# sensors.net
KiCad netlist of a schematic drawn in Altium Designer
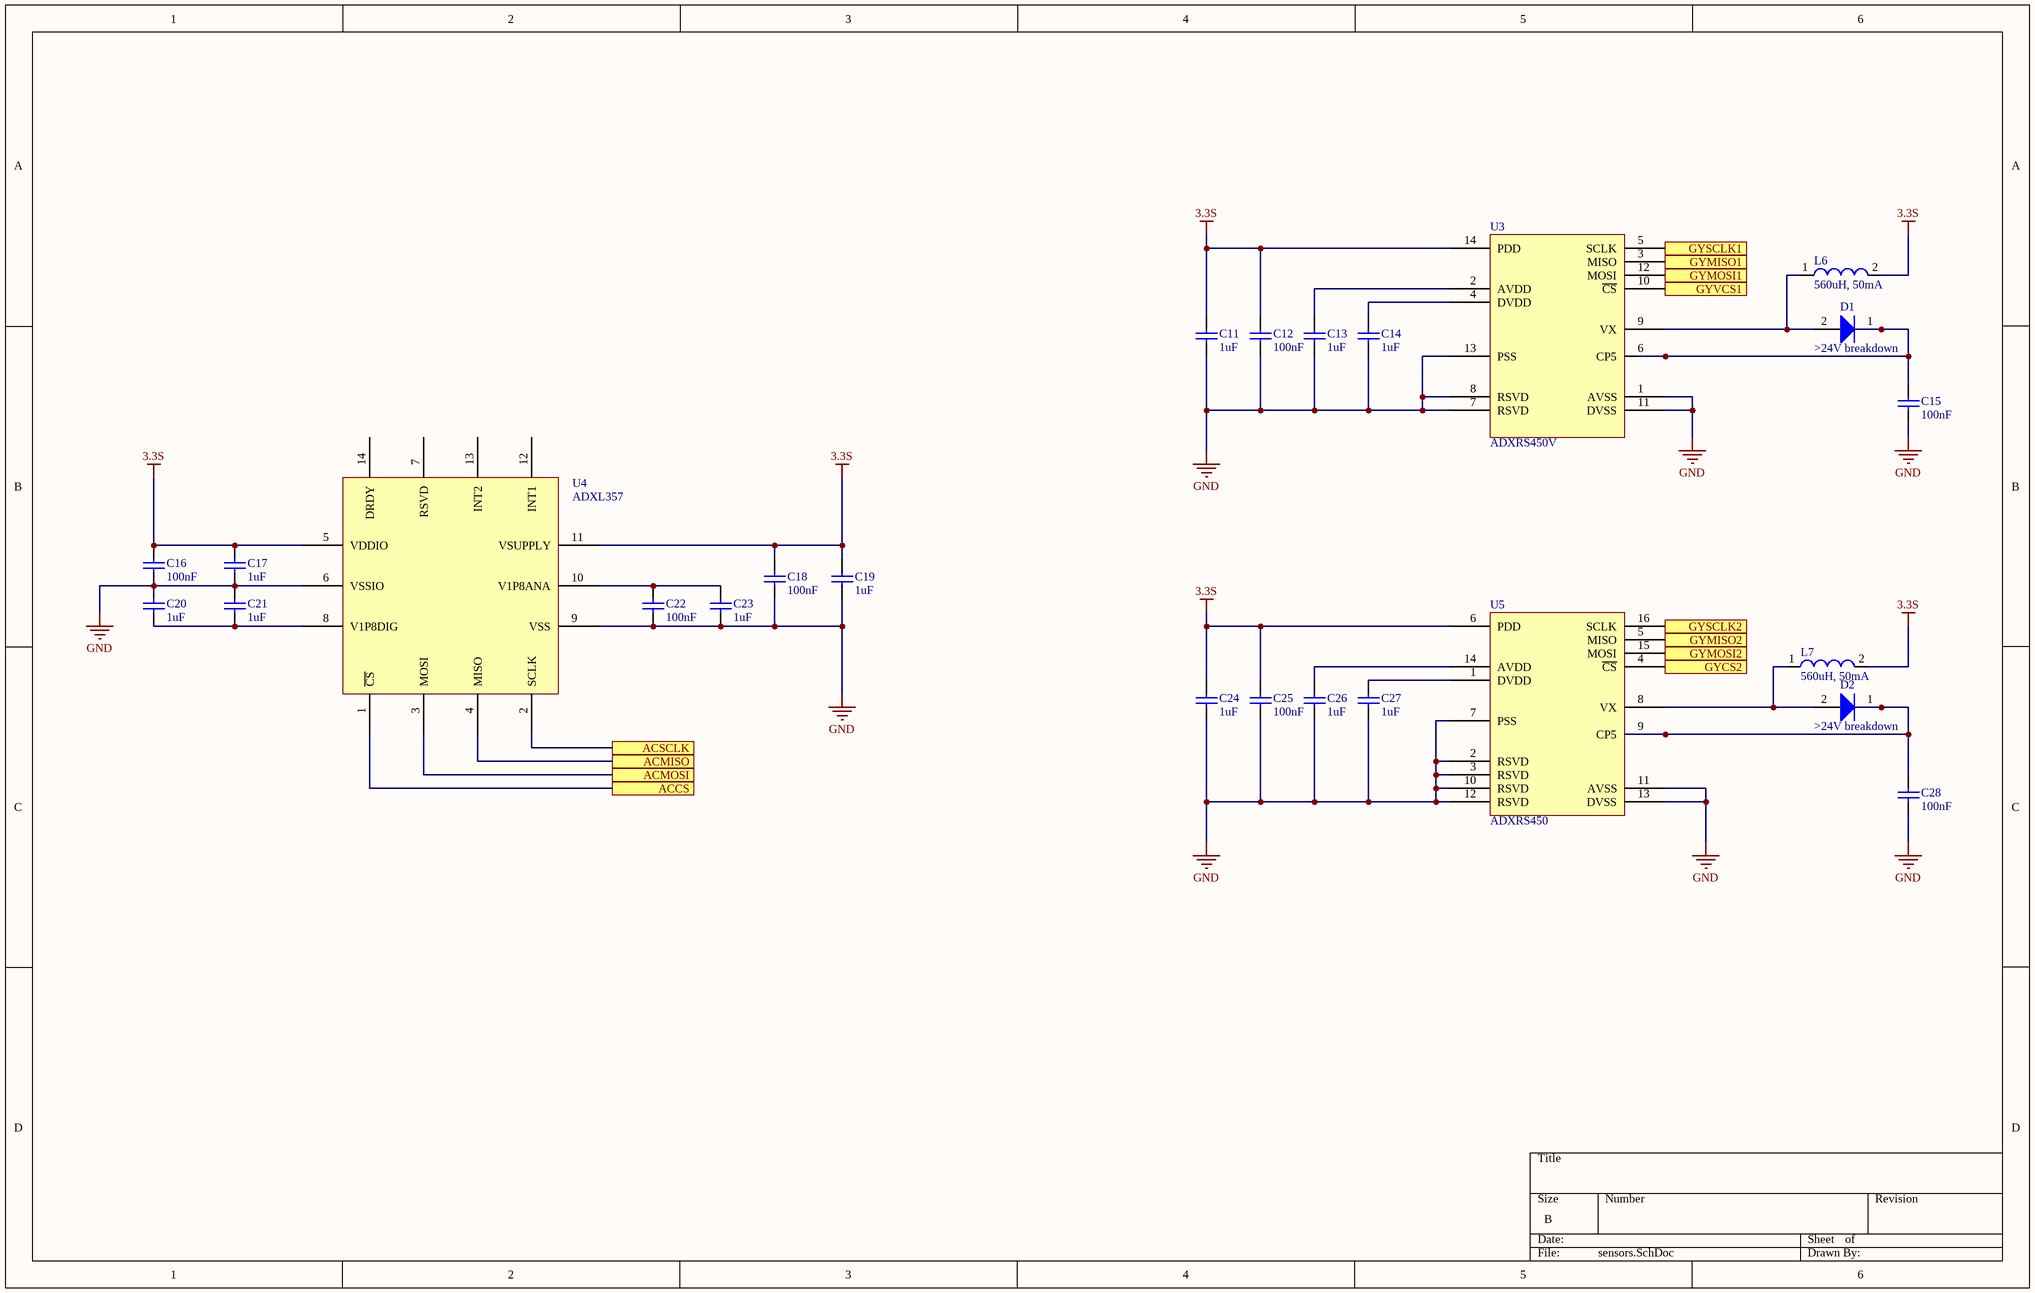
[diagram p0: sensors.SchDoc]

(export (version "E")
  (design (tool "Eeschema 10.0.6"))
  (components
    (comp (ref "C11")
      (value "1uF")
      (footprint "CAPC1709X95X35LL10T25")
      (description "Chip Capacitor, 1 uF, +/- 10%, 50 V, -55 to 125 degC, 0603 (1608 Metric), RoHS, Tape and Reel")
      (fields (field (name "MANUFACTURER") "Taiyo Yuden") (field (name "TOLERANCE") "10%"))
      (libsource (lib "Altium Content Vault") (part "CAP-NP-2"))
    )
    (comp (ref "C12")
      (value "100nF")
      (footprint "CAPC1608X90X40ML10T20")
      (fields (field (name "TOLERANCE") "±10%") (field (name "MANUFACTURER") "Yageo"))
      (libsource (lib "Altium Content Vault") (part "CAP-NP-2"))
    )
    (comp (ref "C13")
      (value "1uF")
      (footprint "CAPC1709X95X35LL10T25")
      (description "Chip Capacitor, 1 uF, +/- 10%, 50 V, -55 to 125 degC, 0603 (1608 Metric), RoHS, Tape and Reel")
      (fields (field (name "MANUFACTURER") "Taiyo Yuden") (field (name "TOLERANCE") "10%"))
      (libsource (lib "Altium Content Vault") (part "CAP-NP-2"))
    )
    (comp (ref "C14")
      (value "1uF")
      (footprint "CAPC1709X95X35LL10T25")
      (description "Chip Capacitor, 1 uF, +/- 10%, 50 V, -55 to 125 degC, 0603 (1608 Metric), RoHS, Tape and Reel")
      (fields (field (name "MANUFACTURER") "Taiyo Yuden") (field (name "TOLERANCE") "10%"))
      (libsource (lib "Altium Content Vault") (part "CAP-NP-2"))
    )
    (comp (ref "C15")
      (value "100nF")
      (footprint "CAPC1608X90X40ML10T20")
      (fields (field (name "TOLERANCE") "±10%") (field (name "MANUFACTURER") "Yageo"))
      (libsource (lib "Altium Content Vault") (part "CAP-NP-2"))
    )
    (comp (ref "C16")
      (value "100nF")
      (footprint "CAPC1608X90X40ML10T20")
      (fields (field (name "TOLERANCE") "±10%") (field (name "MANUFACTURER") "Yageo"))
      (libsource (lib "Altium Content Vault") (part "CAP-NP-2"))
    )
    (comp (ref "C17")
      (value "1uF")
      (footprint "CAPC1709X95X35LL10T25")
      (description "Chip Capacitor, 1 uF, +/- 10%, 50 V, -55 to 125 degC, 0603 (1608 Metric), RoHS, Tape and Reel")
      (fields (field (name "MANUFACTURER") "Taiyo Yuden") (field (name "TOLERANCE") "10%"))
      (libsource (lib "Altium Content Vault") (part "CAP-NP-2"))
    )
    (comp (ref "C18")
      (value "100nF")
      (footprint "CAPC1608X90X40ML10T20")
      (fields (field (name "TOLERANCE") "±10%") (field (name "MANUFACTURER") "Yageo"))
      (libsource (lib "Altium Content Vault") (part "CAP-NP-2"))
    )
    (comp (ref "C19")
      (value "1uF")
      (footprint "CAPC1709X95X35LL10T25")
      (description "Chip Capacitor, 1 uF, +/- 10%, 50 V, -55 to 125 degC, 0603 (1608 Metric), RoHS, Tape and Reel")
      (fields (field (name "MANUFACTURER") "Taiyo Yuden") (field (name "TOLERANCE") "10%"))
      (libsource (lib "Altium Content Vault") (part "CAP-NP-2"))
    )
    (comp (ref "C20")
      (value "1uF")
      (footprint "CAPC1709X95X35LL10T25")
      (description "Chip Capacitor, 1 uF, +/- 10%, 50 V, -55 to 125 degC, 0603 (1608 Metric), RoHS, Tape and Reel")
      (fields (field (name "MANUFACTURER") "Taiyo Yuden") (field (name "TOLERANCE") "10%"))
      (libsource (lib "Altium Content Vault") (part "CAP-NP-2"))
    )
    (comp (ref "C21")
      (value "1uF")
      (footprint "CAPC1709X95X35LL10T25")
      (description "Chip Capacitor, 1 uF, +/- 10%, 50 V, -55 to 125 degC, 0603 (1608 Metric), RoHS, Tape and Reel")
      (fields (field (name "MANUFACTURER") "Taiyo Yuden") (field (name "TOLERANCE") "10%"))
      (libsource (lib "Altium Content Vault") (part "CAP-NP-2"))
    )
    (comp (ref "C22")
      (value "100nF")
      (footprint "CAPC1608X90X40ML10T20")
      (fields (field (name "TOLERANCE") "±10%") (field (name "MANUFACTURER") "Yageo"))
      (libsource (lib "Altium Content Vault") (part "CAP-NP-2"))
    )
    (comp (ref "C23")
      (value "1uF")
      (footprint "CAPC1709X95X35LL10T25")
      (description "Chip Capacitor, 1 uF, +/- 10%, 50 V, -55 to 125 degC, 0603 (1608 Metric), RoHS, Tape and Reel")
      (fields (field (name "MANUFACTURER") "Taiyo Yuden") (field (name "TOLERANCE") "10%"))
      (libsource (lib "Altium Content Vault") (part "CAP-NP-2"))
    )
    (comp (ref "C24")
      (value "1uF")
      (footprint "CAPC1709X95X35LL10T25")
      (description "Chip Capacitor, 1 uF, +/- 10%, 50 V, -55 to 125 degC, 0603 (1608 Metric), RoHS, Tape and Reel")
      (fields (field (name "MANUFACTURER") "Taiyo Yuden") (field (name "TOLERANCE") "10%"))
      (libsource (lib "Altium Content Vault") (part "CAP-NP-2"))
    )
    (comp (ref "C25")
      (value "100nF")
      (footprint "CAPC1608X90X40ML10T20")
      (fields (field (name "TOLERANCE") "±10%") (field (name "MANUFACTURER") "Yageo"))
      (libsource (lib "Altium Content Vault") (part "CAP-NP-2"))
    )
    (comp (ref "C26")
      (value "1uF")
      (footprint "CAPC1709X95X35LL10T25")
      (description "Chip Capacitor, 1 uF, +/- 10%, 50 V, -55 to 125 degC, 0603 (1608 Metric), RoHS, Tape and Reel")
      (fields (field (name "MANUFACTURER") "Taiyo Yuden") (field (name "TOLERANCE") "10%"))
      (libsource (lib "Altium Content Vault") (part "CAP-NP-2"))
    )
    (comp (ref "C27")
      (value "1uF")
      (footprint "CAPC1709X95X35LL10T25")
      (description "Chip Capacitor, 1 uF, +/- 10%, 50 V, -55 to 125 degC, 0603 (1608 Metric), RoHS, Tape and Reel")
      (fields (field (name "MANUFACTURER") "Taiyo Yuden") (field (name "TOLERANCE") "10%"))
      (libsource (lib "Altium Content Vault") (part "CAP-NP-2"))
    )
    (comp (ref "C28")
      (value "100nF")
      (footprint "CAPC1608X90X40ML10T20")
      (fields (field (name "TOLERANCE") "±10%") (field (name "MANUFACTURER") "Yageo"))
      (libsource (lib "Altium Content Vault") (part "CAP-NP-2"))
    )
    (comp (ref "D1")
      (value ">24V breakdown")
      (footprint "ONSC-SOD-323-2-477-02_V")
      (description "Schottky Barrier Diode, 2-Pin SOD-323, Pb-Free, Tape and Reel")
      (fields (field (name "PARTNUMBER") "BAT54HT1G") (field (name "MANUFACTURER") "On Semiconductor"))
      (libsource (lib "Altium Content Vault") (part "ONSC-D-K1A2-2"))
    )
    (comp (ref "D2")
      (value ">24V breakdown")
      (footprint "ONSC-SOD-323-2-477-02_V")
      (description "Schottky Barrier Diode, 2-Pin SOD-323, Pb-Free, Tape and Reel")
      (fields (field (name "PARTNUMBER") "BAT54HT1G") (field (name "MANUFACTURER") "On Semiconductor"))
      (libsource (lib "Altium Content Vault") (part "ONSC-D-K1A2-2"))
    )
    (comp (ref "L6")
      (value "560uH, 50mA")
      (footprint "WE-PD-L")
      (description "SMD-Shielded Power Inductor WE-PD, L = 560 µH")
      (libsource (lib "Altium Content Vault") (part "PAS-IND-INDUCTOR-2"))
    )
    (comp (ref "L7")
      (value "560uH, 50mA")
      (footprint "WE-PD-L")
      (description "SMD-Shielded Power Inductor WE-PD, L = 560 µH")
      (libsource (lib "Altium Content Vault") (part "PAS-IND-INDUCTOR-2"))
    )
    (comp (ref "U3")
      (value "ADXRS450V")
      (footprint "LCC127P900X400X915-14N")
      (libsource (lib "ADXRS450") (part "ADXRS450V"))
    )
    (comp (ref "U4")
      (value "ADXL357")
      (footprint "LCCS127P605X560X220-14N")
      (libsource (lib "ADXL357") (part "ADXL357"))
    )
    (comp (ref "U5")
      (value "ADXRS450")
      (footprint "SOIC127P1040X373-16N")
      (libsource (lib "ADXRS450") (part "ADXRS450"))
    )
  )
  (nets
    (net (code "1") (name "/ACCS") (class "Default")
      (node (ref "U4") (pin "1") (pinfunction "~{CS}_1") (pintype "passive"))
    )
    (net (code "2") (name "/ACMISO") (class "Default")
      (node (ref "U4") (pin "4") (pinfunction "MISO_4") (pintype "passive"))
    )
    (net (code "3") (name "/ACMOSI") (class "Default")
      (node (ref "U4") (pin "3") (pinfunction "MOSI_3") (pintype "passive"))
    )
    (net (code "4") (name "/ACSCLK") (class "Default")
      (node (ref "U4") (pin "2") (pinfunction "SCLK_2") (pintype "passive"))
    )
    (net (code "5") (name "/GYCS2") (class "Default")
      (node (ref "U5") (pin "4") (pinfunction "~{CS}_4") (pintype "passive"))
    )
    (net (code "6") (name "/GYMISO1") (class "Default")
      (node (ref "U3") (pin "3") (pinfunction "MISO_3") (pintype "passive"))
    )
    (net (code "7") (name "/GYMISO2") (class "Default")
      (node (ref "U5") (pin "5") (pinfunction "MISO_5") (pintype "passive"))
    )
    (net (code "8") (name "/GYMOSI1") (class "Default")
      (node (ref "U3") (pin "12") (pinfunction "MOSI_12") (pintype "passive"))
    )
    (net (code "9") (name "/GYMOSI2") (class "Default")
      (node (ref "U5") (pin "15") (pinfunction "MOSI_15") (pintype "passive"))
    )
    (net (code "10") (name "/GYSCLK1") (class "Default")
      (node (ref "U3") (pin "5") (pinfunction "SCLK_5") (pintype "passive"))
    )
    (net (code "11") (name "/GYSCLK2") (class "Default")
      (node (ref "U5") (pin "16") (pinfunction "SCLK_16") (pintype "passive"))
    )
    (net (code "12") (name "/GYVCS1") (class "Default")
      (node (ref "U3") (pin "10") (pinfunction "~{CS}_10") (pintype "passive"))
    )
    (net (code "13") (name "3.3S") (class "Default")
      (node (ref "C11") (pin "2") (pinfunction "2_2") (pintype "passive"))
      (node (ref "C12") (pin "2") (pinfunction "2_2") (pintype "passive"))
      (node (ref "C16") (pin "1") (pinfunction "1_1") (pintype "passive"))
      (node (ref "C17") (pin "2") (pinfunction "2_2") (pintype "passive"))
      (node (ref "C18") (pin "1") (pinfunction "1_1") (pintype "passive"))
      (node (ref "C19") (pin "2") (pinfunction "2_2") (pintype "passive"))
      (node (ref "C24") (pin "2") (pinfunction "2_2") (pintype "passive"))
      (node (ref "C25") (pin "2") (pinfunction "2_2") (pintype "passive"))
      (node (ref "L6") (pin "2") (pinfunction "2_2") (pintype "passive"))
      (node (ref "L7") (pin "2") (pinfunction "2_2") (pintype "passive"))
      (node (ref "U3") (pin "14") (pinfunction "PDD_14") (pintype "passive"))
      (node (ref "U4") (pin "11") (pinfunction "VSUPPLY_11") (pintype "passive"))
      (node (ref "U4") (pin "5") (pinfunction "VDDIO_5") (pintype "passive"))
      (node (ref "U5") (pin "6") (pinfunction "PDD_6") (pintype "passive"))
    )
    (net (code "14") (name "GND") (class "Default")
      (node (ref "C11") (pin "1") (pinfunction "1_1") (pintype "passive"))
      (node (ref "C12") (pin "1") (pinfunction "1_1") (pintype "passive"))
      (node (ref "C13") (pin "1") (pinfunction "1_1") (pintype "passive"))
      (node (ref "C14") (pin "1") (pinfunction "1_1") (pintype "passive"))
      (node (ref "C15") (pin "1") (pinfunction "1_1") (pintype "passive"))
      (node (ref "C16") (pin "2") (pinfunction "2_2") (pintype "passive"))
      (node (ref "C17") (pin "1") (pinfunction "1_1") (pintype "passive"))
      (node (ref "C18") (pin "2") (pinfunction "2_2") (pintype "passive"))
      (node (ref "C19") (pin "1") (pinfunction "1_1") (pintype "passive"))
      (node (ref "C20") (pin "2") (pinfunction "2_2") (pintype "passive"))
      (node (ref "C21") (pin "2") (pinfunction "2_2") (pintype "passive"))
      (node (ref "C22") (pin "2") (pinfunction "2_2") (pintype "passive"))
      (node (ref "C23") (pin "1") (pinfunction "1_1") (pintype "passive"))
      (node (ref "C24") (pin "1") (pinfunction "1_1") (pintype "passive"))
      (node (ref "C25") (pin "1") (pinfunction "1_1") (pintype "passive"))
      (node (ref "C26") (pin "1") (pinfunction "1_1") (pintype "passive"))
      (node (ref "C27") (pin "1") (pinfunction "1_1") (pintype "passive"))
      (node (ref "C28") (pin "1") (pinfunction "1_1") (pintype "passive"))
      (node (ref "U3") (pin "1") (pinfunction "AVSS_1") (pintype "passive"))
      (node (ref "U3") (pin "11") (pinfunction "DVSS_11") (pintype "passive"))
      (node (ref "U3") (pin "13") (pinfunction "PSS_13") (pintype "passive"))
      (node (ref "U3") (pin "7") (pinfunction "RSVD_7") (pintype "passive"))
      (node (ref "U3") (pin "8") (pinfunction "RSVD_8") (pintype "passive"))
      (node (ref "U4") (pin "6") (pinfunction "VSSIO_6") (pintype "passive"))
      (node (ref "U4") (pin "9") (pinfunction "VSS_9") (pintype "passive"))
      (node (ref "U5") (pin "10") (pinfunction "RSVD_10") (pintype "passive"))
      (node (ref "U5") (pin "11") (pinfunction "AVSS_11") (pintype "passive"))
      (node (ref "U5") (pin "12") (pinfunction "RSVD_12") (pintype "passive"))
      (node (ref "U5") (pin "13") (pinfunction "DVSS_13") (pintype "passive"))
      (node (ref "U5") (pin "2") (pinfunction "RSVD_2") (pintype "passive"))
      (node (ref "U5") (pin "3") (pinfunction "RSVD_3") (pintype "passive"))
      (node (ref "U5") (pin "7") (pinfunction "PSS_7") (pintype "passive"))
    )
    (net (code "15") (name "Net-(D1-A)") (class "Default")
      (node (ref "D1") (pin "2") (pinfunction "A_2") (pintype "passive"))
      (node (ref "L6") (pin "1") (pinfunction "1_1") (pintype "passive"))
      (node (ref "U3") (pin "9") (pinfunction "VX_9") (pintype "passive"))
    )
    (net (code "16") (name "Net-(D1-K)") (class "Default")
      (node (ref "C15") (pin "2") (pinfunction "2_2") (pintype "passive"))
      (node (ref "D1") (pin "1") (pinfunction "K_1") (pintype "passive"))
      (node (ref "U3") (pin "6") (pinfunction "CP5_6") (pintype "passive"))
    )
    (net (code "17") (name "Net-(D2-A)") (class "Default")
      (node (ref "D2") (pin "2") (pinfunction "A_2") (pintype "passive"))
      (node (ref "L7") (pin "1") (pinfunction "1_1") (pintype "passive"))
      (node (ref "U5") (pin "8") (pinfunction "VX_8") (pintype "passive"))
    )
    (net (code "18") (name "Net-(D2-K)") (class "Default")
      (node (ref "C28") (pin "2") (pinfunction "2_2") (pintype "passive"))
      (node (ref "D2") (pin "1") (pinfunction "K_1") (pintype "passive"))
      (node (ref "U5") (pin "9") (pinfunction "CP5_9") (pintype "passive"))
    )
    (net (code "19") (name "Net-(U3-AVDD)") (class "Default")
      (node (ref "C13") (pin "2") (pinfunction "2_2") (pintype "passive"))
      (node (ref "U3") (pin "2") (pinfunction "AVDD_2") (pintype "passive"))
    )
    (net (code "20") (name "Net-(U3-DVDD)") (class "Default")
      (node (ref "C14") (pin "2") (pinfunction "2_2") (pintype "passive"))
      (node (ref "U3") (pin "4") (pinfunction "DVDD_4") (pintype "passive"))
    )
    (net (code "21") (name "Net-(U4-V1P8ANA)") (class "Default")
      (node (ref "C22") (pin "1") (pinfunction "1_1") (pintype "passive"))
      (node (ref "C23") (pin "2") (pinfunction "2_2") (pintype "passive"))
      (node (ref "U4") (pin "10") (pinfunction "V1P8ANA_10") (pintype "passive"))
    )
    (net (code "22") (name "Net-(U4-V1P8DIG)") (class "Default")
      (node (ref "C20") (pin "1") (pinfunction "1_1") (pintype "passive"))
      (node (ref "C21") (pin "1") (pinfunction "1_1") (pintype "passive"))
      (node (ref "U4") (pin "8") (pinfunction "V1P8DIG_8") (pintype "passive"))
    )
    (net (code "23") (name "Net-(U5-AVDD)") (class "Default")
      (node (ref "C26") (pin "2") (pinfunction "2_2") (pintype "passive"))
      (node (ref "U5") (pin "14") (pinfunction "AVDD_14") (pintype "passive"))
    )
    (net (code "24") (name "Net-(U5-DVDD)") (class "Default")
      (node (ref "C27") (pin "2") (pinfunction "2_2") (pintype "passive"))
      (node (ref "U5") (pin "1") (pinfunction "DVDD_1") (pintype "passive"))
    )
    (net (code "25") (name "unconnected-(U4-DRDY-Pad14)") (class "Default")
      (node (ref "U4") (pin "14") (pinfunction "DRDY_14") (pintype "passive"))
    )
    (net (code "26") (name "unconnected-(U4-INT1-Pad12)") (class "Default")
      (node (ref "U4") (pin "12") (pinfunction "INT1_12") (pintype "passive"))
    )
    (net (code "27") (name "unconnected-(U4-INT2-Pad13)") (class "Default")
      (node (ref "U4") (pin "13") (pinfunction "INT2_13") (pintype "passive"))
    )
    (net (code "28") (name "unconnected-(U4-RSVD-Pad7)") (class "Default")
      (node (ref "U4") (pin "7") (pinfunction "RSVD_7") (pintype "passive"))
    )
  )
)
